# MayBanNuocTuDong.net
KiCad netlist of a schematic drawn in Altium Designer
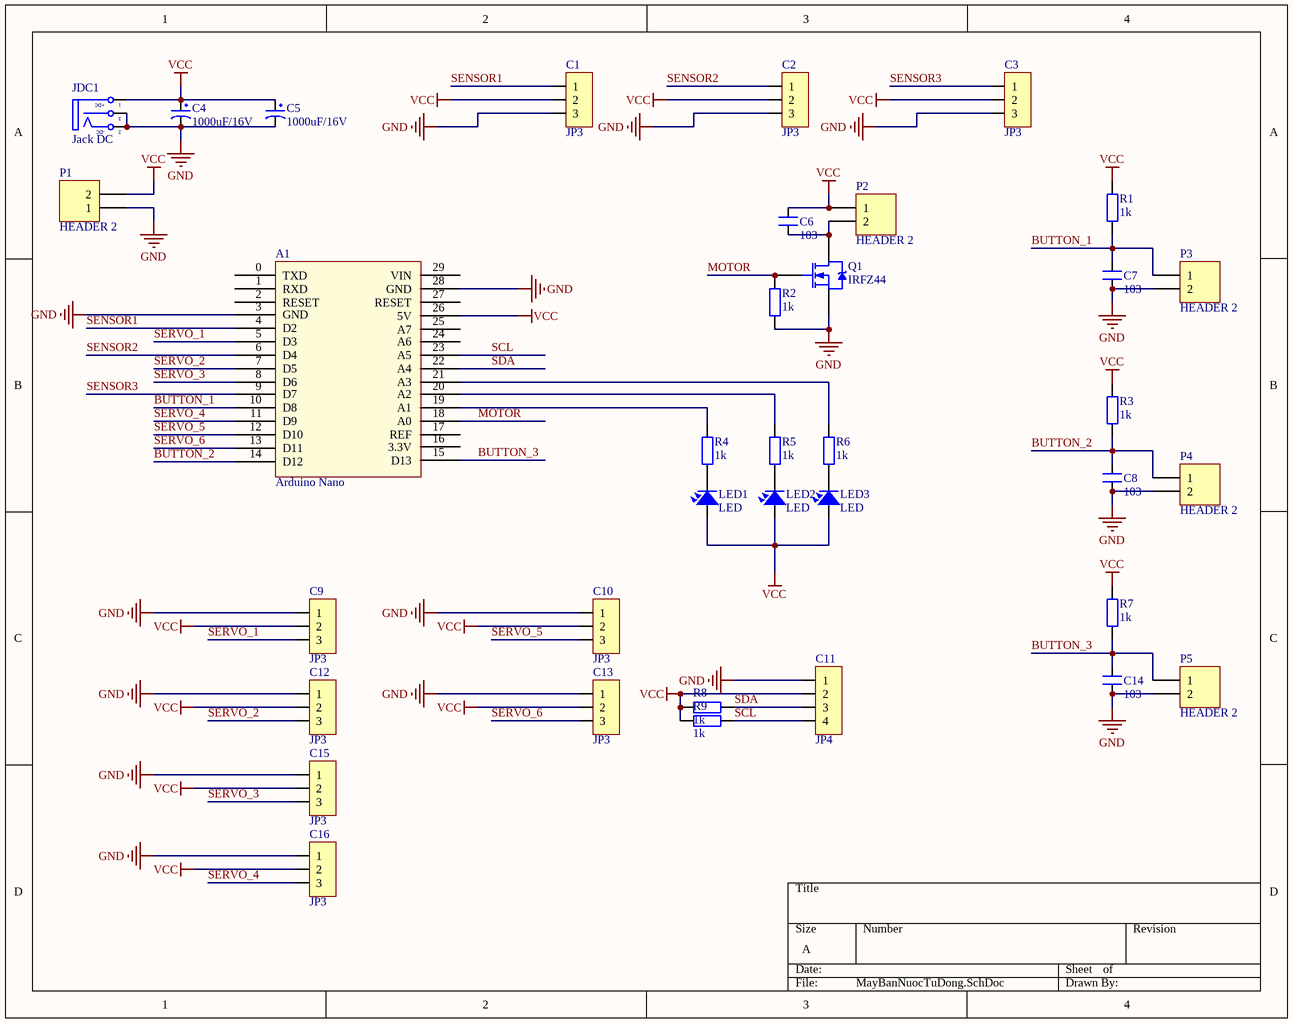
[diagram p0: MayBanNuocTuDong.SchDoc]

(export (version "E")
  (design (tool "Eeschema 10.0.6"))
  (components
    (comp (ref "A1")
      (value "Arduino Nano")
      (footprint "Arduino Nano")
      (libsource (lib "OBIT_TESLA") (part "Arduino Nano"))
    )
    (comp (ref "C1")
      (value "JP3")
      (footprint "JP3-D1T")
      (description "WR-PHD 2.54 mm Angled Socket Header")
      (fields
        (field (name "MANUFACTURER") "Würth Elektronik eiSos GmbH")
        (field (name "PARTNO") "613003143121")
        (field (name "CREATED BY") "Karrer Zheng")
      )
      (libsource (lib "OBIT_TESLA") (part "JP3"))
    )
    (comp (ref "C2")
      (value "JP3")
      (footprint "JP3-D1T")
      (description "WR-PHD 2.54 mm Angled Socket Header")
      (fields
        (field (name "MANUFACTURER") "Würth Elektronik eiSos GmbH")
        (field (name "PARTNO") "613003143121")
        (field (name "CREATED BY") "Karrer Zheng")
      )
      (libsource (lib "OBIT_TESLA") (part "JP3"))
    )
    (comp (ref "C3")
      (value "JP3")
      (footprint "JP3-D1T")
      (description "WR-PHD 2.54 mm Angled Socket Header")
      (fields
        (field (name "MANUFACTURER") "Würth Elektronik eiSos GmbH")
        (field (name "PARTNO") "613003143121")
        (field (name "CREATED BY") "Karrer Zheng")
      )
      (libsource (lib "OBIT_TESLA") (part "JP3"))
    )
    (comp (ref "C4")
      (value "1000uF/16V")
      (footprint "CP1.5/3.4")
      (description "Cap 1000uF/16V - 220uF/50V")
      (libsource (lib "OBIT_TESLA") (part "CP4"))
    )
    (comp (ref "C5")
      (value "1000uF/16V")
      (footprint "CP1.5/3.4")
      (description "Cap 1000uF/16V - 220uF/50V")
      (libsource (lib "OBIT_TESLA") (part "CP4"))
    )
    (comp (ref "C6")
      (value "103")
      (footprint "SM-0805")
      (description "Cap SMD")
      (libsource (lib "OBIT_TESLA") (part "CM"))
    )
    (comp (ref "C7")
      (value "103")
      (footprint "SM-0805")
      (description "Cap SMD")
      (libsource (lib "OBIT_TESLA") (part "CM"))
    )
    (comp (ref "C8")
      (value "103")
      (footprint "SM-0805")
      (description "Cap SMD")
      (libsource (lib "OBIT_TESLA") (part "CM"))
    )
    (comp (ref "C9")
      (value "JP3")
      (footprint "JP3-D1T")
      (description "WR-PHD 2.54 mm Angled Socket Header")
      (fields
        (field (name "MANUFACTURER") "Würth Elektronik eiSos GmbH")
        (field (name "PARTNO") "613003143121")
        (field (name "CREATED BY") "Karrer Zheng")
      )
      (libsource (lib "OBIT_TESLA") (part "JP3"))
    )
    (comp (ref "C10")
      (value "JP3")
      (footprint "JP3-D1T")
      (description "WR-PHD 2.54 mm Angled Socket Header")
      (fields
        (field (name "MANUFACTURER") "Würth Elektronik eiSos GmbH")
        (field (name "PARTNO") "613003143121")
        (field (name "CREATED BY") "Karrer Zheng")
      )
      (libsource (lib "OBIT_TESLA") (part "JP3"))
    )
    (comp (ref "C11")
      (value "JP4")
      (footprint "JP4-C1T")
      (description "WR-PHD 2.54 mm Angled Socket Header")
      (fields
        (field (name "MANUFACTURER") "Würth Elektronik eiSos GmbH")
        (field (name "PARTNO") "613004143121")
        (field (name "CREATED BY") "Karrer Zheng")
      )
      (libsource (lib "OBIT_TESLA") (part "JP4"))
    )
    (comp (ref "C12")
      (value "JP3")
      (footprint "JP3-D1T")
      (description "WR-PHD 2.54 mm Angled Socket Header")
      (fields
        (field (name "MANUFACTURER") "Würth Elektronik eiSos GmbH")
        (field (name "PARTNO") "613003143121")
        (field (name "CREATED BY") "Karrer Zheng")
      )
      (libsource (lib "OBIT_TESLA") (part "JP3"))
    )
    (comp (ref "C13")
      (value "JP3")
      (footprint "JP3-D1T")
      (description "WR-PHD 2.54 mm Angled Socket Header")
      (fields
        (field (name "MANUFACTURER") "Würth Elektronik eiSos GmbH")
        (field (name "PARTNO") "613003143121")
        (field (name "CREATED BY") "Karrer Zheng")
      )
      (libsource (lib "OBIT_TESLA") (part "JP3"))
    )
    (comp (ref "C14")
      (value "103")
      (footprint "SM-0805")
      (description "Cap SMD")
      (libsource (lib "OBIT_TESLA") (part "CM"))
    )
    (comp (ref "C15")
      (value "JP3")
      (footprint "JP3-D1T")
      (description "WR-PHD 2.54 mm Angled Socket Header")
      (fields
        (field (name "MANUFACTURER") "Würth Elektronik eiSos GmbH")
        (field (name "PARTNO") "613003143121")
        (field (name "CREATED BY") "Karrer Zheng")
      )
      (libsource (lib "OBIT_TESLA") (part "JP3"))
    )
    (comp (ref "C16")
      (value "JP3")
      (footprint "JP3-D1T")
      (description "WR-PHD 2.54 mm Angled Socket Header")
      (fields
        (field (name "MANUFACTURER") "Würth Elektronik eiSos GmbH")
        (field (name "PARTNO") "613003143121")
        (field (name "CREATED BY") "Karrer Zheng")
      )
      (libsource (lib "OBIT_TESLA") (part "JP3"))
    )
    (comp (ref "JDC1") (value "Jack DC") (footprint "DC0") (libsource (lib "OBIT_TESLA") (part "JACK_DC")))
    (comp (ref "LED1") (value "LED") (footprint "LED-5-BLUE") (libsource (lib "OBIT_TESLA") (part "LED")))
    (comp (ref "LED2") (value "LED") (footprint "LED-5-BLUE") (libsource (lib "OBIT_TESLA") (part "LED")))
    (comp (ref "LED3") (value "LED") (footprint "LED-5-BLUE") (libsource (lib "OBIT_TESLA") (part "LED")))
    (comp (ref "P1") (value "HEADER 2") (footprint "CON 2") (libsource (lib "OBIT_TESLA") (part "HEADER 2")))
    (comp (ref "P2") (value "HEADER 2") (footprint "CON 2") (libsource (lib "") (part "HEADER 2_1")))
    (comp (ref "P3") (value "HEADER 2") (footprint "CON 2") (libsource (lib "") (part "HEADER 2_1")))
    (comp (ref "P4") (value "HEADER 2") (footprint "CON 2") (libsource (lib "") (part "HEADER 2_1")))
    (comp (ref "P5") (value "HEADER 2") (footprint "CON 2") (libsource (lib "") (part "HEADER 2_1")))
    (comp (ref "Q1") (value "IRFZ44") (footprint "TO252-123") (libsource (lib "OBIT_TESLA") (part "IRFZ44")))
    (comp (ref "R1")
      (value "1k")
      (footprint "RES-SMD-0805")
      (description "Resistor R1/4W")
      (libsource (lib "OBIT_TESLA") (part "R"))
    )
    (comp (ref "R2")
      (value "1k")
      (footprint "RES-SMD-0805")
      (description "Resistor R1/4W")
      (libsource (lib "OBIT_TESLA") (part "R"))
    )
    (comp (ref "R3")
      (value "1k")
      (footprint "RES-SMD-0805")
      (description "Resistor R1/4W")
      (libsource (lib "OBIT_TESLA") (part "R"))
    )
    (comp (ref "R4")
      (value "1k")
      (footprint "RES-SMD-0805")
      (description "Resistor R1/4W")
      (libsource (lib "OBIT_TESLA") (part "R"))
    )
    (comp (ref "R5")
      (value "1k")
      (footprint "RES-SMD-0805")
      (description "Resistor R1/4W")
      (libsource (lib "OBIT_TESLA") (part "R"))
    )
    (comp (ref "R6")
      (value "1k")
      (footprint "RES-SMD-0805")
      (description "Resistor R1/4W")
      (libsource (lib "OBIT_TESLA") (part "R"))
    )
    (comp (ref "R7")
      (value "1k")
      (footprint "RES-SMD-0805")
      (description "Resistor R1/4W")
      (libsource (lib "OBIT_TESLA") (part "R"))
    )
    (comp (ref "R8")
      (value "1k")
      (footprint "RES-SMD-0805")
      (description "Resistor R1/4W")
      (libsource (lib "OBIT_TESLA") (part "R"))
    )
    (comp (ref "R9")
      (value "1k")
      (footprint "RES-SMD-0805")
      (description "Resistor R1/4W")
      (libsource (lib "OBIT_TESLA") (part "R"))
    )
  )
  (nets
    (net (code "1") (name "/BUTTON_1") (class "Default")
      (node (ref "A1") (pin "10") (pinfunction "D8_10") (pintype "passive"))
      (node (ref "C7") (pin "2") (pinfunction "2_2") (pintype "passive"))
      (node (ref "P3") (pin "1") (pinfunction "1_1") (pintype "passive"))
      (node (ref "R1") (pin "1") (pinfunction "1_1") (pintype "passive"))
    )
    (net (code "2") (name "/BUTTON_2") (class "Default")
      (node (ref "A1") (pin "14") (pinfunction "D12_14") (pintype "passive"))
      (node (ref "C8") (pin "2") (pinfunction "2_2") (pintype "passive"))
      (node (ref "P4") (pin "1") (pinfunction "1_1") (pintype "passive"))
      (node (ref "R3") (pin "1") (pinfunction "1_1") (pintype "passive"))
    )
    (net (code "3") (name "/BUTTON_3") (class "Default")
      (node (ref "A1") (pin "15") (pinfunction "D13_15") (pintype "passive"))
      (node (ref "C14") (pin "2") (pinfunction "2_2") (pintype "passive"))
      (node (ref "P5") (pin "1") (pinfunction "1_1") (pintype "passive"))
      (node (ref "R7") (pin "1") (pinfunction "1_1") (pintype "passive"))
    )
    (net (code "4") (name "/MOTOR") (class "Default")
      (node (ref "A1") (pin "18") (pinfunction "A0_18") (pintype "passive"))
      (node (ref "Q1") (pin "1") (pinfunction "G_1") (pintype "passive"))
      (node (ref "R2") (pin "2") (pinfunction "2_2") (pintype "passive"))
    )
    (net (code "5") (name "/SCL") (class "Default")
      (node (ref "A1") (pin "23") (pinfunction "A5_23") (pintype "passive"))
      (node (ref "C11") (pin "4") (pinfunction "4_4") (pintype "passive"))
      (node (ref "R9") (pin "1") (pinfunction "1_1") (pintype "passive"))
    )
    (net (code "6") (name "/SDA") (class "Default")
      (node (ref "A1") (pin "22") (pinfunction "A4_22") (pintype "passive"))
      (node (ref "C11") (pin "3") (pinfunction "3_3") (pintype "passive"))
      (node (ref "R8") (pin "1") (pinfunction "1_1") (pintype "passive"))
    )
    (net (code "7") (name "/SENSOR1") (class "Default")
      (node (ref "A1") (pin "4") (pinfunction "D2_4") (pintype "passive"))
      (node (ref "C1") (pin "1") (pinfunction "1_1") (pintype "passive"))
    )
    (net (code "8") (name "/SENSOR2") (class "Default")
      (node (ref "A1") (pin "6") (pinfunction "D4_6") (pintype "passive"))
      (node (ref "C2") (pin "1") (pinfunction "1_1") (pintype "passive"))
    )
    (net (code "9") (name "/SENSOR3") (class "Default")
      (node (ref "A1") (pin "9") (pinfunction "D7_9") (pintype "passive"))
      (node (ref "C3") (pin "1") (pinfunction "1_1") (pintype "passive"))
    )
    (net (code "10") (name "/SERVO_1") (class "Default")
      (node (ref "A1") (pin "5") (pinfunction "D3_5") (pintype "passive"))
      (node (ref "C9") (pin "3") (pinfunction "3_3") (pintype "passive"))
    )
    (net (code "11") (name "/SERVO_2") (class "Default")
      (node (ref "A1") (pin "7") (pinfunction "D5_7") (pintype "passive"))
      (node (ref "C12") (pin "3") (pinfunction "3_3") (pintype "passive"))
    )
    (net (code "12") (name "/SERVO_3") (class "Default")
      (node (ref "A1") (pin "8") (pinfunction "D6_8") (pintype "passive"))
      (node (ref "C15") (pin "3") (pinfunction "3_3") (pintype "passive"))
    )
    (net (code "13") (name "/SERVO_4") (class "Default")
      (node (ref "A1") (pin "11") (pinfunction "D9_11") (pintype "passive"))
      (node (ref "C16") (pin "3") (pinfunction "3_3") (pintype "passive"))
    )
    (net (code "14") (name "/SERVO_5") (class "Default")
      (node (ref "A1") (pin "12") (pinfunction "D10_12") (pintype "passive"))
      (node (ref "C10") (pin "3") (pinfunction "3_3") (pintype "passive"))
    )
    (net (code "15") (name "/SERVO_6") (class "Default")
      (node (ref "A1") (pin "13") (pinfunction "D11_13") (pintype "passive"))
      (node (ref "C13") (pin "3") (pinfunction "3_3") (pintype "passive"))
    )
    (net (code "16") (name "GND") (class "Default")
      (node (ref "A1") (pin "28") (pinfunction "GND_28") (pintype "passive"))
      (node (ref "A1") (pin "3") (pinfunction "GND_3") (pintype "passive"))
      (node (ref "C1") (pin "3") (pinfunction "3_3") (pintype "passive"))
      (node (ref "C10") (pin "1") (pinfunction "1_1") (pintype "passive"))
      (node (ref "C11") (pin "1") (pinfunction "1_1") (pintype "passive"))
      (node (ref "C12") (pin "1") (pinfunction "1_1") (pintype "passive"))
      (node (ref "C13") (pin "1") (pinfunction "1_1") (pintype "passive"))
      (node (ref "C14") (pin "1") (pinfunction "1_1") (pintype "passive"))
      (node (ref "C15") (pin "1") (pinfunction "1_1") (pintype "passive"))
      (node (ref "C16") (pin "1") (pinfunction "1_1") (pintype "passive"))
      (node (ref "C2") (pin "3") (pinfunction "3_3") (pintype "passive"))
      (node (ref "C3") (pin "3") (pinfunction "3_3") (pintype "passive"))
      (node (ref "C4") (pin "2") (pinfunction "2_2") (pintype "passive"))
      (node (ref "C5") (pin "2") (pinfunction "2_2") (pintype "passive"))
      (node (ref "C7") (pin "1") (pinfunction "1_1") (pintype "passive"))
      (node (ref "C8") (pin "1") (pinfunction "1_1") (pintype "passive"))
      (node (ref "C9") (pin "1") (pinfunction "1_1") (pintype "passive"))
      (node (ref "JDC1") (pin "2") (pinfunction "TN_2") (pintype "passive"))
      (node (ref "JDC1") (pin "3") (pinfunction "S_3") (pintype "power_in"))
      (node (ref "P1") (pin "1") (pinfunction "1_1") (pintype "passive"))
      (node (ref "P3") (pin "2") (pinfunction "2_2") (pintype "passive"))
      (node (ref "P4") (pin "2") (pinfunction "2_2") (pintype "passive"))
      (node (ref "P5") (pin "2") (pinfunction "2_2") (pintype "passive"))
      (node (ref "Q1") (pin "3") (pinfunction "S_3") (pintype "passive"))
      (node (ref "R2") (pin "1") (pinfunction "1_1") (pintype "passive"))
    )
    (net (code "17") (name "Net-(A1-A1)") (class "Default")
      (node (ref "A1") (pin "19") (pinfunction "A1_19") (pintype "passive"))
      (node (ref "R4") (pin "2") (pinfunction "2_2") (pintype "passive"))
    )
    (net (code "18") (name "Net-(A1-A2)") (class "Default")
      (node (ref "A1") (pin "20") (pinfunction "A2_20") (pintype "passive"))
      (node (ref "R5") (pin "2") (pinfunction "2_2") (pintype "passive"))
    )
    (net (code "19") (name "Net-(A1-A3)") (class "Default")
      (node (ref "A1") (pin "21") (pinfunction "A3_21") (pintype "passive"))
      (node (ref "R6") (pin "2") (pinfunction "2_2") (pintype "passive"))
    )
    (net (code "20") (name "Net-(LED1-Pad2)") (class "Default")
      (node (ref "LED1") (pin "2") (pinfunction "2_2") (pintype "passive"))
      (node (ref "R4") (pin "1") (pinfunction "1_1") (pintype "passive"))
    )
    (net (code "21") (name "Net-(LED2-Pad2)") (class "Default")
      (node (ref "LED2") (pin "2") (pinfunction "2_2") (pintype "passive"))
      (node (ref "R5") (pin "1") (pinfunction "1_1") (pintype "passive"))
    )
    (net (code "22") (name "Net-(LED3-Pad2)") (class "Default")
      (node (ref "LED3") (pin "2") (pinfunction "2_2") (pintype "passive"))
      (node (ref "R6") (pin "1") (pinfunction "1_1") (pintype "passive"))
    )
    (net (code "23") (name "Net-(Q1-D)") (class "Default")
      (node (ref "C6") (pin "1") (pinfunction "1_1") (pintype "passive"))
      (node (ref "P2") (pin "2") (pinfunction "2_2") (pintype "passive"))
      (node (ref "Q1") (pin "2") (pinfunction "D_2") (pintype "passive"))
    )
    (net (code "24") (name "VCC") (class "Default")
      (node (ref "A1") (pin "26") (pinfunction "5V_26") (pintype "passive"))
      (node (ref "C1") (pin "2") (pinfunction "2_2") (pintype "passive"))
      (node (ref "C10") (pin "2") (pinfunction "2_2") (pintype "passive"))
      (node (ref "C11") (pin "2") (pinfunction "2_2") (pintype "passive"))
      (node (ref "C12") (pin "2") (pinfunction "2_2") (pintype "passive"))
      (node (ref "C13") (pin "2") (pinfunction "2_2") (pintype "passive"))
      (node (ref "C15") (pin "2") (pinfunction "2_2") (pintype "passive"))
      (node (ref "C16") (pin "2") (pinfunction "2_2") (pintype "passive"))
      (node (ref "C2") (pin "2") (pinfunction "2_2") (pintype "passive"))
      (node (ref "C3") (pin "2") (pinfunction "2_2") (pintype "passive"))
      (node (ref "C4") (pin "1") (pinfunction "1_1") (pintype "passive"))
      (node (ref "C5") (pin "1") (pinfunction "1_1") (pintype "passive"))
      (node (ref "C6") (pin "2") (pinfunction "2_2") (pintype "passive"))
      (node (ref "C9") (pin "2") (pinfunction "2_2") (pintype "passive"))
      (node (ref "JDC1") (pin "1") (pinfunction "T_1") (pintype "passive"))
      (node (ref "LED1") (pin "1") (pinfunction "1_1") (pintype "passive"))
      (node (ref "LED2") (pin "1") (pinfunction "1_1") (pintype "passive"))
      (node (ref "LED3") (pin "1") (pinfunction "1_1") (pintype "passive"))
      (node (ref "P1") (pin "2") (pinfunction "2_2") (pintype "passive"))
      (node (ref "P2") (pin "1") (pinfunction "1_1") (pintype "passive"))
      (node (ref "R1") (pin "2") (pinfunction "2_2") (pintype "passive"))
      (node (ref "R3") (pin "2") (pinfunction "2_2") (pintype "passive"))
      (node (ref "R7") (pin "2") (pinfunction "2_2") (pintype "passive"))
      (node (ref "R8") (pin "2") (pinfunction "2_2") (pintype "passive"))
      (node (ref "R9") (pin "2") (pinfunction "2_2") (pintype "passive"))
    )
    (net (code "25") (name "unconnected-(A1-3.3V-Pad16)") (class "Default")
      (node (ref "A1") (pin "16") (pinfunction "3.3V_16") (pintype "passive"))
    )
    (net (code "26") (name "unconnected-(A1-A6-Pad24)") (class "Default")
      (node (ref "A1") (pin "24") (pinfunction "A6_24") (pintype "passive"))
    )
    (net (code "27") (name "unconnected-(A1-A7-Pad25)") (class "Default")
      (node (ref "A1") (pin "25") (pinfunction "A7_25") (pintype "passive"))
    )
    (net (code "28") (name "unconnected-(A1-REF-Pad17)") (class "Default")
      (node (ref "A1") (pin "17") (pinfunction "REF_17") (pintype "passive"))
    )
    (net (code "29") (name "unconnected-(A1-RESET-Pad2)") (class "Default")
      (node (ref "A1") (pin "2") (pinfunction "RESET_2") (pintype "passive"))
    )
    (net (code "30") (name "unconnected-(A1-RESET-Pad27)") (class "Default")
      (node (ref "A1") (pin "27") (pinfunction "RESET_27") (pintype "passive"))
    )
    (net (code "31") (name "unconnected-(A1-RXD-Pad1)") (class "Default")
      (node (ref "A1") (pin "1") (pinfunction "RXD_1") (pintype "passive"))
    )
    (net (code "32") (name "unconnected-(A1-TXD-Pad0)") (class "Default")
      (node (ref "A1") (pin "0") (pinfunction "TXD_0") (pintype "passive"))
    )
    (net (code "33") (name "unconnected-(A1-VIN-Pad29)") (class "Default")
      (node (ref "A1") (pin "29") (pinfunction "VIN_29") (pintype "passive"))
    )
  )
)
